# de9-2x5.net
KiCad netlist of a schematic drawn in EAGLE
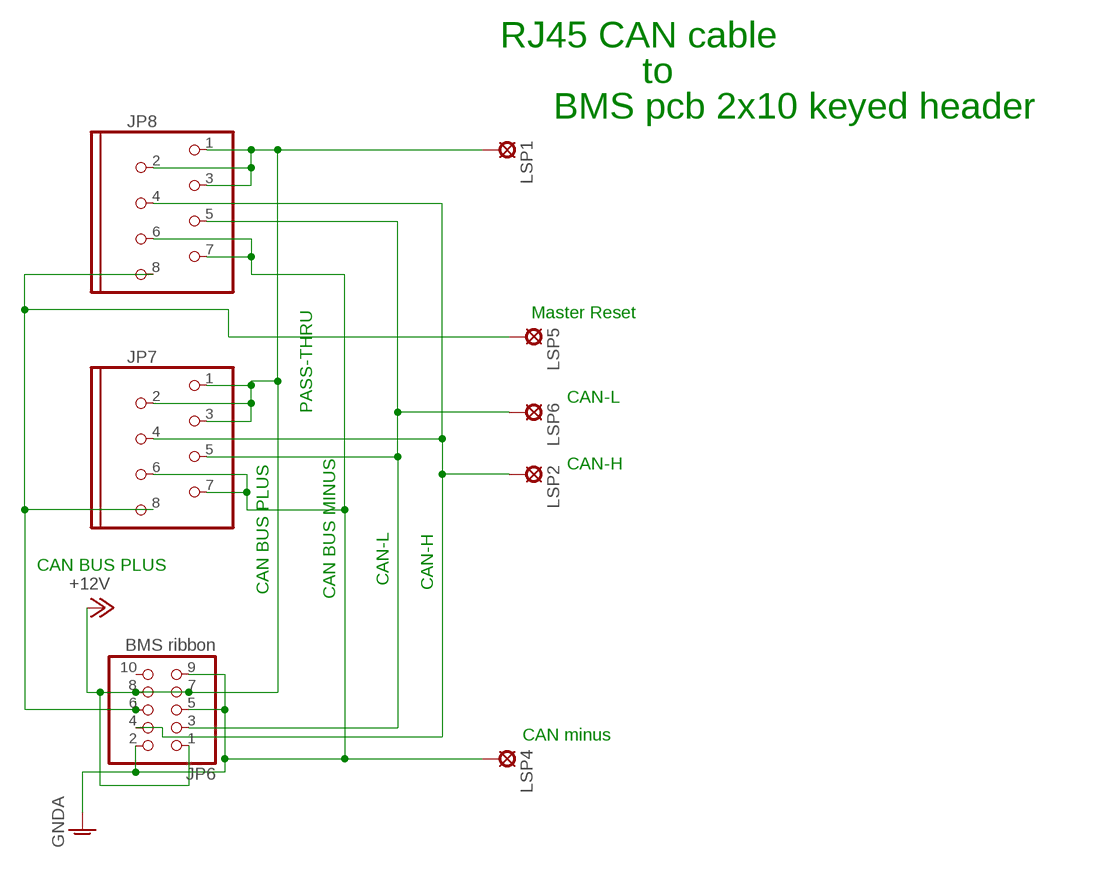
[diagram p0: schematic, sheet 1]

(export (version "E")
  (design (tool "Eeschema 10.0.6"))
  (components
    (comp (ref "JP6")
      (value "BMS ribbon")
      (footprint "eagle-import:2X05_KEYED")
      (libsource (lib "eagle-import") (part "PINHD-2X5_KEYED"))
    )
    (comp (ref "JP7")
      (value "MOD8P8C")
      (footprint "eagle-import:MOD8P8C")
      (libsource (lib "eagle-import") (part "MOD8P8C"))
    )
    (comp (ref "JP8")
      (value "MOD8P8C")
      (footprint "eagle-import:MOD8P8C")
      (libsource (lib "eagle-import") (part "MOD8P8C"))
    )
    (comp (ref "LSP1")
      (value "SE14")
      (footprint "eagle-import:SE14")
      (libsource (lib "eagle-import") (part "SE14"))
    )
    (comp (ref "LSP2")
      (value "LSP10")
      (footprint "eagle-import:LSP10")
      (libsource (lib "eagle-import") (part "LSP10"))
    )
    (comp (ref "LSP4")
      (value "SE14")
      (footprint "eagle-import:SE14")
      (libsource (lib "eagle-import") (part "SE14"))
    )
    (comp (ref "LSP5")
      (value "LSP10")
      (footprint "eagle-import:LSP10")
      (libsource (lib "eagle-import") (part "LSP10"))
    )
    (comp (ref "LSP6")
      (value "LSP10")
      (footprint "eagle-import:LSP10")
      (libsource (lib "eagle-import") (part "LSP10"))
    )
  )
  (nets
    (net (code "1") (name "+12V") (class "Default")
      (node (ref "JP6") (pin "1") (pinfunction "1_1") (pintype "passive"))
      (node (ref "JP6") (pin "7") (pinfunction "7_7") (pintype "passive"))
      (node (ref "JP6") (pin "8") (pinfunction "8_8") (pintype "passive"))
      (node (ref "JP7") (pin "1") (pinfunction "1_1") (pintype "passive"))
      (node (ref "JP7") (pin "2") (pinfunction "5_2") (pintype "passive"))
      (node (ref "JP7") (pin "3") (pinfunction "2_3") (pintype "passive"))
      (node (ref "JP8") (pin "1") (pinfunction "1_1") (pintype "passive"))
      (node (ref "JP8") (pin "2") (pinfunction "5_2") (pintype "passive"))
      (node (ref "JP8") (pin "3") (pinfunction "2_3") (pintype "passive"))
      (node (ref "LSP1") (pin "MP") (pinfunction "MP_MP") (pintype "passive"))
    )
    (net (code "2") (name "GNDA") (class "Default")
      (node (ref "JP6") (pin "2") (pinfunction "2_2") (pintype "passive"))
      (node (ref "JP6") (pin "5") (pinfunction "5_5") (pintype "passive"))
      (node (ref "JP6") (pin "9") (pinfunction "9_9") (pintype "passive"))
      (node (ref "JP7") (pin "6") (pinfunction "7_6") (pintype "passive"))
      (node (ref "JP7") (pin "7") (pinfunction "4_7") (pintype "passive"))
      (node (ref "JP8") (pin "6") (pinfunction "7_6") (pintype "passive"))
      (node (ref "JP8") (pin "7") (pinfunction "4_7") (pintype "passive"))
      (node (ref "LSP4") (pin "MP") (pinfunction "MP_MP") (pintype "passive"))
    )
    (net (code "3") (name "Net-(JP6-Pad6)") (class "Default")
      (node (ref "JP6") (pin "6") (pinfunction "6_6") (pintype "passive"))
      (node (ref "JP7") (pin "8") (pinfunction "8_8") (pintype "passive"))
      (node (ref "JP8") (pin "8") (pinfunction "8_8") (pintype "passive"))
      (node (ref "LSP5") (pin "MP") (pinfunction "MP_MP") (pintype "passive"))
    )
    (net (code "4") (name "Net-(JP7-3)") (class "Default")
      (node (ref "JP6") (pin "3") (pinfunction "3_3") (pintype "passive"))
      (node (ref "JP7") (pin "5") (pinfunction "3_5") (pintype "passive"))
      (node (ref "JP8") (pin "5") (pinfunction "3_5") (pintype "passive"))
      (node (ref "LSP6") (pin "MP") (pinfunction "MP_MP") (pintype "passive"))
    )
    (net (code "5") (name "Net-(JP7-6)") (class "Default")
      (node (ref "JP6") (pin "4") (pinfunction "4_4") (pintype "passive"))
      (node (ref "JP7") (pin "4") (pinfunction "6_4") (pintype "passive"))
      (node (ref "JP8") (pin "4") (pinfunction "6_4") (pintype "passive"))
      (node (ref "LSP2") (pin "MP") (pinfunction "MP_MP") (pintype "passive"))
    )
    (net (code "6") (name "unconnected-(JP6-Pad10)") (class "Default")
      (node (ref "JP6") (pin "10") (pinfunction "10_10") (pintype "passive"))
    )
  )
)
